# relay-unit-XRF.net
KiCad netlist of a schematic drawn in EAGLE
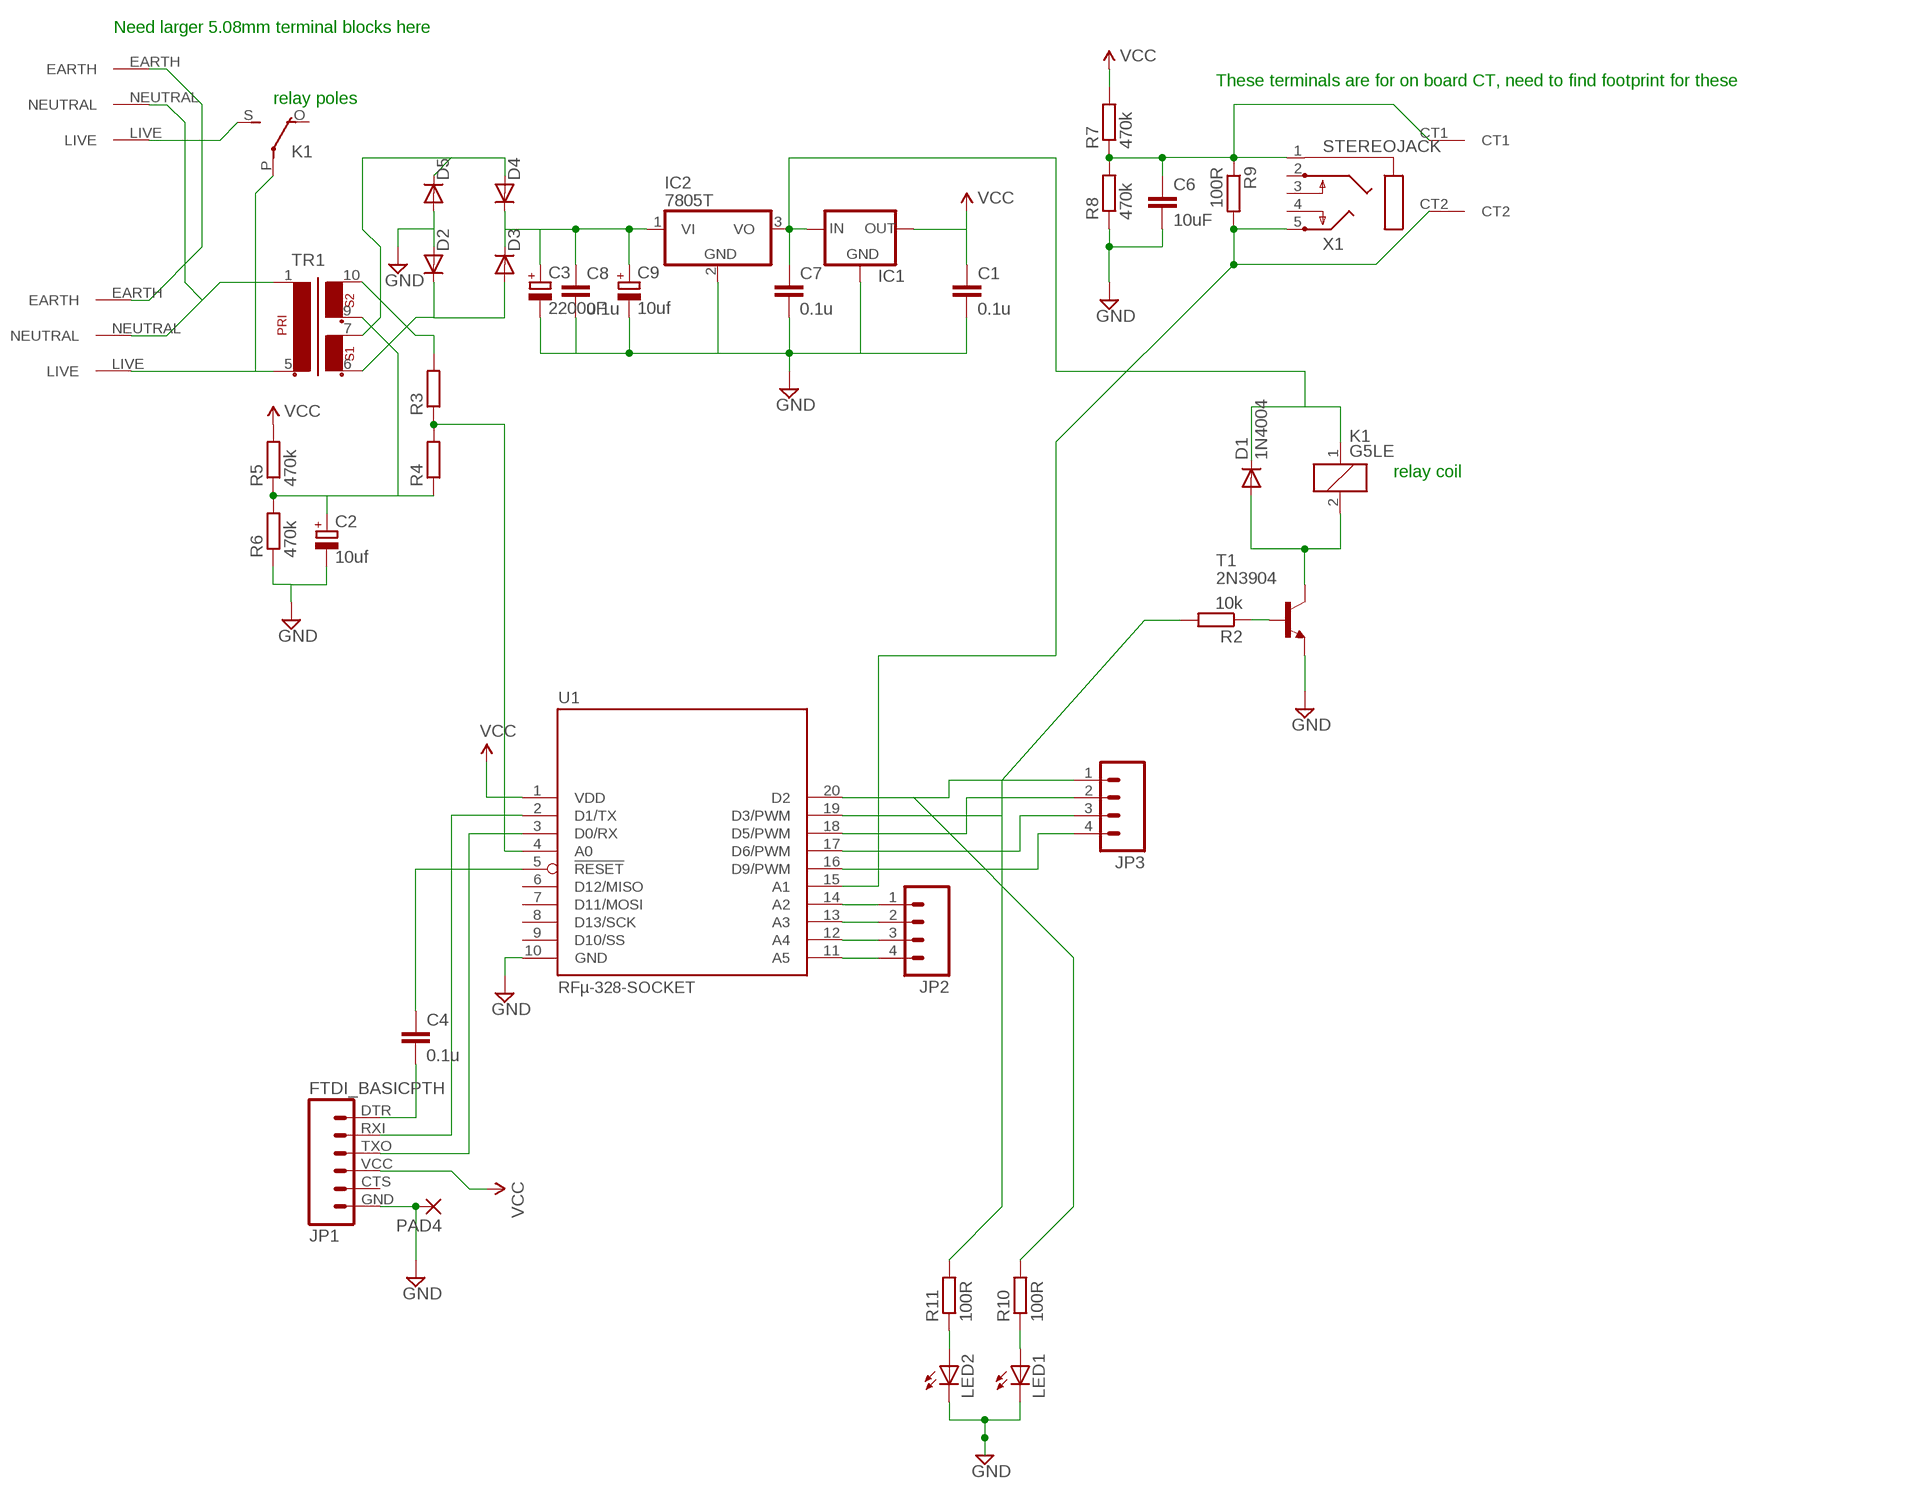
[diagram p0: schematic, sheet 1]

(export (version "E")
  (design (tool "Eeschema 10.0.6"))
  (components
    (comp (ref "C1")
      (value "0.1u")
      (footprint "eagle-import:C025-024X044")
      (libsource (lib "eagle-import") (part "C-EU025-024X044"))
    )
    (comp (ref "C2")
      (value "10uf")
      (footprint "eagle-import:E1,8-4")
      (libsource (lib "eagle-import") (part "CPOL-EUE1.8-4"))
    )
    (comp (ref "C3")
      (value "2200uF")
      (footprint "eagle-import:E5-13")
      (libsource (lib "eagle-import") (part "CPOL-EUE5-13"))
    )
    (comp (ref "C4")
      (value "0.1u")
      (footprint "eagle-import:C025-024X044")
      (libsource (lib "eagle-import") (part "C-EU025-024X044"))
    )
    (comp (ref "C6")
      (value "10uF")
      (footprint "eagle-import:C025-024X044")
      (libsource (lib "eagle-import") (part "C-EU025-024X044"))
    )
    (comp (ref "C7")
      (value "0.1u")
      (footprint "eagle-import:C025-024X044")
      (libsource (lib "eagle-import") (part "C-EU025-024X044"))
    )
    (comp (ref "C8")
      (value "0.1u")
      (footprint "eagle-import:C025-024X044")
      (libsource (lib "eagle-import") (part "C-EU025-024X044"))
    )
    (comp (ref "C9")
      (value "10uf")
      (footprint "eagle-import:E1,8-4")
      (libsource (lib "eagle-import") (part "CPOL-EUE1.8-4"))
    )
    (comp (ref "D1")
      (value "1N4004")
      (footprint "eagle-import:DO41-10")
      (libsource (lib "eagle-import") (part "1N4004"))
    )
    (comp (ref "D2")
      (value "1N4004")
      (footprint "eagle-import:DO41-10")
      (libsource (lib "eagle-import") (part "1N4004"))
    )
    (comp (ref "D3")
      (value "1N4004")
      (footprint "eagle-import:DO41-10")
      (libsource (lib "eagle-import") (part "1N4004"))
    )
    (comp (ref "D4")
      (value "1N4004")
      (footprint "eagle-import:DO41-10")
      (libsource (lib "eagle-import") (part "1N4004"))
    )
    (comp (ref "D5")
      (value "1N4004")
      (footprint "eagle-import:DO41-10")
      (libsource (lib "eagle-import") (part "1N4004"))
    )
    (comp (ref "IC1")
      (value "MCP1700TRI")
      (footprint "eagle-import:TO92")
      (libsource (lib "eagle-import") (part "MCP1700TRI"))
    )
    (comp (ref "IC2")
      (value "7805T")
      (footprint "eagle-import:TO220H")
      (libsource (lib "eagle-import") (part "78T05"))
    )
    (comp (ref "JP1")
      (value "FTDI_BASICPTH")
      (footprint "eagle-import:FTDI_BASIC")
      (libsource (lib "eagle-import") (part "FTDI_BASICPTH"))
    )
    (comp (ref "JP2")
      (value "M04PTH")
      (footprint "eagle-import:1X04")
      (libsource (lib "eagle-import") (part "M04PTH"))
    )
    (comp (ref "JP3")
      (value "M04PTH")
      (footprint "eagle-import:1X04")
      (libsource (lib "eagle-import") (part "M04PTH"))
    )
    (comp (ref "K1")
      (value "G5LE")
      (footprint "eagle-import:G5LE")
      (libsource (lib "eagle-import") (part "G5LE"))
    )
    (comp (ref "LED1")
      (value "LED3MM")
      (footprint "eagle-import:LED3MM")
      (libsource (lib "eagle-import") (part "LED3MM"))
    )
    (comp (ref "LED2")
      (value "LED3MM")
      (footprint "eagle-import:LED3MM")
      (libsource (lib "eagle-import") (part "LED3MM"))
    )
    (comp (ref "PAD4")
      (value "1,6/0,8")
      (footprint "eagle-import:1,6_0,8")
      (libsource (lib "eagle-import") (part "1,6/0,8"))
    )
    (comp (ref "R2")
      (value "10k")
      (footprint "eagle-import:0204_7")
      (libsource (lib "eagle-import") (part "R-EU_0204/7"))
    )
    (comp (ref "R3")
      (value "R-EU_0204/7")
      (footprint "eagle-import:0204_7")
      (libsource (lib "eagle-import") (part "R-EU_0204/7"))
    )
    (comp (ref "R4")
      (value "R-EU_0204/7")
      (footprint "eagle-import:0204_7")
      (libsource (lib "eagle-import") (part "R-EU_0204/7"))
    )
    (comp (ref "R5")
      (value "470k")
      (footprint "eagle-import:0204_7")
      (libsource (lib "eagle-import") (part "R-EU_0204/7"))
    )
    (comp (ref "R6")
      (value "470k")
      (footprint "eagle-import:0204_7")
      (libsource (lib "eagle-import") (part "R-EU_0204/7"))
    )
    (comp (ref "R7")
      (value "470k")
      (footprint "eagle-import:0204_7")
      (libsource (lib "eagle-import") (part "R-EU_0204/7"))
    )
    (comp (ref "R8")
      (value "470k")
      (footprint "eagle-import:0204_7")
      (libsource (lib "eagle-import") (part "R-EU_0204/7"))
    )
    (comp (ref "R9")
      (value "100R")
      (footprint "eagle-import:0204_7")
      (libsource (lib "eagle-import") (part "R-EU_0204/7"))
    )
    (comp (ref "R10")
      (value "100R")
      (footprint "eagle-import:0204_7")
      (libsource (lib "eagle-import") (part "R-EU_0204/7"))
    )
    (comp (ref "R11")
      (value "100R")
      (footprint "eagle-import:0204_7")
      (libsource (lib "eagle-import") (part "R-EU_0204/7"))
    )
    (comp (ref "T1")
      (value "2N3904")
      (footprint "eagle-import:TO92")
      (libsource (lib "eagle-import") (part "2N3904"))
    )
    (comp (ref "TR1")
      (value "EI30-2")
      (footprint "eagle-import:EI30-2")
      (libsource (lib "eagle-import") (part "EI30-2"))
    )
    (comp (ref "U$1")
      (value "TESTTEST")
      (footprint "eagle-import:TEST")
      (libsource (lib "eagle-import") (part "TESTTEST"))
    )
    (comp (ref "U$2")
      (value "AC_IN")
      (footprint "eagle-import:AC_IN")
      (libsource (lib "eagle-import") (part "AC_IN"))
    )
    (comp (ref "U$3") (value "CT") (footprint "eagle-import:CT") (libsource (lib "eagle-import") (part "CT")))
    (comp (ref "U1")
      (value "RFµ-328-SOCKET")
      (footprint "eagle-import:RFµ-328-SOCKET")
      (libsource (lib "eagle-import") (part "RFµ-328-SOCKET"))
    )
    (comp (ref "X1")
      (value "STEREOJACK")
      (footprint "eagle-import:STX3100")
      (libsource (lib "eagle-import") (part "STEREOJACK"))
    )
  )
  (nets
    (net (code "1") (name "GND") (class "Default")
      (node (ref "C1") (pin "2") (pinfunction "2_2") (pintype "passive"))
      (node (ref "C2") (pin "-") (pinfunction "-_-") (pintype "passive"))
      (node (ref "C3") (pin "-") (pinfunction "-_-") (pintype "passive"))
      (node (ref "C6") (pin "2") (pinfunction "2_2") (pintype "passive"))
      (node (ref "C7") (pin "2") (pinfunction "2_2") (pintype "passive"))
      (node (ref "C8") (pin "2") (pinfunction "2_2") (pintype "passive"))
      (node (ref "C9") (pin "-") (pinfunction "-_-") (pintype "passive"))
      (node (ref "D2") (pin "A") (pinfunction "A_A") (pintype "passive"))
      (node (ref "D5") (pin "A") (pinfunction "A_A") (pintype "passive"))
      (node (ref "IC1") (pin "1") (pinfunction "GND_1") (pintype "input"))
      (node (ref "IC2") (pin "2") (pinfunction "GND_2") (pintype "passive"))
      (node (ref "JP1") (pin "GND") (pinfunction "6_GND") (pintype "passive"))
      (node (ref "LED1") (pin "K") (pinfunction "C_K") (pintype "passive"))
      (node (ref "LED2") (pin "K") (pinfunction "C_K") (pintype "passive"))
      (node (ref "PAD4") (pin "1") (pinfunction "P_1") (pintype "passive"))
      (node (ref "R6") (pin "1") (pinfunction "1_1") (pintype "passive"))
      (node (ref "R8") (pin "1") (pinfunction "1_1") (pintype "passive"))
      (node (ref "T1") (pin "3") (pinfunction "E_3") (pintype "passive"))
      (node (ref "U1") (pin "10") (pinfunction "GND_10") (pintype "power_in"))
    )
    (net (code "2") (name "Net-(C6-Pad1)") (class "Default")
      (node (ref "C6") (pin "1") (pinfunction "1_1") (pintype "passive"))
      (node (ref "R7") (pin "1") (pinfunction "1_1") (pintype "passive"))
      (node (ref "R8") (pin "2") (pinfunction "2_2") (pintype "passive"))
      (node (ref "R9") (pin "1") (pinfunction "1_1") (pintype "passive"))
      (node (ref "U$3") (pin "CT1") (pinfunction "CT1_CT1") (pintype "bidirectional"))
      (node (ref "X1") (pin "1") (pinfunction "1_1") (pintype "passive"))
    )
    (net (code "3") (name "Net-(IC1-IN)") (class "Default")
      (node (ref "C7") (pin "1") (pinfunction "1_1") (pintype "passive"))
      (node (ref "D1") (pin "C") (pinfunction "C_C") (pintype "passive"))
      (node (ref "IC1") (pin "2") (pinfunction "IN_2") (pintype "input"))
      (node (ref "IC2") (pin "3") (pinfunction "VO_3") (pintype "passive"))
      (node (ref "K1") (pin "1") (pinfunction "1_1") (pintype "passive"))
    )
    (net (code "4") (name "Net-(IC2-VI)") (class "Default")
      (node (ref "C3") (pin "+") (pinfunction "+_+") (pintype "passive"))
      (node (ref "C8") (pin "1") (pinfunction "1_1") (pintype "passive"))
      (node (ref "C9") (pin "+") (pinfunction "+_+") (pintype "passive"))
      (node (ref "D3") (pin "C") (pinfunction "C_C") (pintype "passive"))
      (node (ref "D4") (pin "C") (pinfunction "C_C") (pintype "passive"))
      (node (ref "IC2") (pin "1") (pinfunction "VI_1") (pintype "input"))
    )
    (net (code "5") (name "Net-(JP1-1)") (class "Default")
      (node (ref "C4") (pin "2") (pinfunction "2_2") (pintype "passive"))
      (node (ref "JP1") (pin "DTR") (pinfunction "1_DTR") (pintype "passive"))
    )
    (net (code "6") (name "Net-(JP1-2)") (class "Default")
      (node (ref "JP1") (pin "RXI") (pinfunction "2_RXI") (pintype "passive"))
      (node (ref "U1") (pin "2") (pinfunction "D1/TX_2") (pintype "output"))
    )
    (net (code "7") (name "Net-(JP1-3)") (class "Default")
      (node (ref "JP1") (pin "TXO") (pinfunction "3_TXO") (pintype "passive"))
      (node (ref "U1") (pin "3") (pinfunction "D0/RX_3") (pintype "input"))
    )
    (net (code "8") (name "Net-(K1-PadS)") (class "Default")
      (node (ref "K1") (pin "S") (pinfunction "S_S") (pintype "passive"))
      (node (ref "U$1") (pin "LIVE") (pinfunction "LIVE_LIVE") (pintype "input"))
    )
    (net (code "9") (name "Net-(LED1-PadA)") (class "Default")
      (node (ref "LED1") (pin "A") (pinfunction "A_A") (pintype "passive"))
      (node (ref "R10") (pin "1") (pinfunction "1_1") (pintype "passive"))
    )
    (net (code "10") (name "Net-(LED2-PadA)") (class "Default")
      (node (ref "LED2") (pin "A") (pinfunction "A_A") (pintype "passive"))
      (node (ref "R11") (pin "1") (pinfunction "1_1") (pintype "passive"))
    )
    (net (code "11") (name "Net-(T1-B)") (class "Default")
      (node (ref "R2") (pin "1") (pinfunction "1_1") (pintype "passive"))
      (node (ref "T1") (pin "2") (pinfunction "B_2") (pintype "passive"))
    )
    (net (code "12") (name "Net-(T1-C)") (class "Default")
      (node (ref "D1") (pin "A") (pinfunction "A_A") (pintype "passive"))
      (node (ref "K1") (pin "2") (pinfunction "2_2") (pintype "passive"))
      (node (ref "T1") (pin "1") (pinfunction "C_1") (pintype "passive"))
    )
    (net (code "13") (name "Net-(TR1-2)") (class "Default")
      (node (ref "K1") (pin "P") (pinfunction "P_P") (pintype "passive"))
      (node (ref "TR1") (pin "5") (pinfunction "2_5") (pintype "passive"))
      (node (ref "U$2") (pin "LIVE") (pinfunction "LIVE_LIVE") (pintype "bidirectional"))
    )
    (net (code "14") (name "Net-(TR1-3)") (class "Default")
      (node (ref "D2") (pin "C") (pinfunction "C_C") (pintype "passive"))
      (node (ref "D3") (pin "A") (pinfunction "A_A") (pintype "passive"))
      (node (ref "TR1") (pin "6") (pinfunction "3_6") (pintype "passive"))
    )
    (net (code "15") (name "Net-(TR1-4)") (class "Default")
      (node (ref "D4") (pin "A") (pinfunction "A_A") (pintype "passive"))
      (node (ref "D5") (pin "C") (pinfunction "C_C") (pintype "passive"))
      (node (ref "TR1") (pin "7") (pinfunction "4_7") (pintype "passive"))
    )
    (net (code "16") (name "Net-(TR1-5)") (class "Default")
      (node (ref "C2") (pin "+") (pinfunction "+_+") (pintype "passive"))
      (node (ref "R4") (pin "1") (pinfunction "1_1") (pintype "passive"))
      (node (ref "R5") (pin "1") (pinfunction "1_1") (pintype "passive"))
      (node (ref "R6") (pin "2") (pinfunction "2_2") (pintype "passive"))
      (node (ref "TR1") (pin "9") (pinfunction "5_9") (pintype "passive"))
    )
    (net (code "17") (name "Net-(TR1-6)") (class "Default")
      (node (ref "R3") (pin "2") (pinfunction "2_2") (pintype "passive"))
      (node (ref "TR1") (pin "10") (pinfunction "6_10") (pintype "passive"))
    )
    (net (code "18") (name "Net-(TR1-Pad1)") (class "Default")
      (node (ref "TR1") (pin "1") (pinfunction "1_1") (pintype "passive"))
      (node (ref "U$1") (pin "NEUTRAL") (pinfunction "NEUTRAL_NEUTRAL") (pintype "input"))
      (node (ref "U$2") (pin "NEUTRAL") (pinfunction "NEUTRAL_NEUTRAL") (pintype "bidirectional"))
    )
    (net (code "19") (name "Net-(U$1-PadEARTH)") (class "Default")
      (node (ref "U$1") (pin "EARTH") (pinfunction "EARTH_EARTH") (pintype "input"))
      (node (ref "U$2") (pin "EARTH") (pinfunction "EARTH_EARTH") (pintype "bidirectional"))
    )
    (net (code "20") (name "Net-(U1-A0)") (class "Default")
      (node (ref "R3") (pin "1") (pinfunction "1_1") (pintype "passive"))
      (node (ref "R4") (pin "2") (pinfunction "2_2") (pintype "passive"))
      (node (ref "U1") (pin "4") (pinfunction "A0_4") (pintype "bidirectional"))
    )
    (net (code "21") (name "Net-(U1-A1)") (class "Default")
      (node (ref "R9") (pin "2") (pinfunction "2_2") (pintype "passive"))
      (node (ref "U$3") (pin "CT2") (pinfunction "CT2_CT2") (pintype "bidirectional"))
      (node (ref "U1") (pin "15") (pinfunction "A1_15") (pintype "bidirectional"))
      (node (ref "X1") (pin "5") (pinfunction "5_5") (pintype "passive"))
    )
    (net (code "22") (name "Net-(U1-A2)") (class "Default")
      (node (ref "JP2") (pin "1") (pinfunction "1_1") (pintype "passive"))
      (node (ref "U1") (pin "14") (pinfunction "A2_14") (pintype "bidirectional"))
    )
    (net (code "23") (name "Net-(U1-A3)") (class "Default")
      (node (ref "JP2") (pin "2") (pinfunction "2_2") (pintype "passive"))
      (node (ref "U1") (pin "13") (pinfunction "A3_13") (pintype "bidirectional"))
    )
    (net (code "24") (name "Net-(U1-A4)") (class "Default")
      (node (ref "JP2") (pin "3") (pinfunction "3_3") (pintype "passive"))
      (node (ref "U1") (pin "12") (pinfunction "A4_12") (pintype "output"))
    )
    (net (code "25") (name "Net-(U1-A5)") (class "Default")
      (node (ref "JP2") (pin "4") (pinfunction "4_4") (pintype "passive"))
      (node (ref "U1") (pin "11") (pinfunction "A5_11") (pintype "bidirectional"))
    )
    (net (code "26") (name "Net-(U1-D2)") (class "Default")
      (node (ref "JP3") (pin "1") (pinfunction "1_1") (pintype "passive"))
      (node (ref "R10") (pin "2") (pinfunction "2_2") (pintype "passive"))
      (node (ref "U1") (pin "20") (pinfunction "D2_20") (pintype "bidirectional"))
    )
    (net (code "27") (name "Net-(U1-D3{slash}PWM)") (class "Default")
      (node (ref "R11") (pin "2") (pinfunction "2_2") (pintype "passive"))
      (node (ref "R2") (pin "2") (pinfunction "2_2") (pintype "passive"))
      (node (ref "U1") (pin "19") (pinfunction "D3/PWM_19") (pintype "bidirectional"))
    )
    (net (code "28") (name "Net-(U1-D5{slash}PWM)") (class "Default")
      (node (ref "JP3") (pin "2") (pinfunction "2_2") (pintype "passive"))
      (node (ref "U1") (pin "18") (pinfunction "D5/PWM_18") (pintype "bidirectional"))
    )
    (net (code "29") (name "Net-(U1-D6{slash}PWM)") (class "Default")
      (node (ref "JP3") (pin "3") (pinfunction "3_3") (pintype "passive"))
      (node (ref "U1") (pin "17") (pinfunction "D6/PWM_17") (pintype "bidirectional"))
    )
    (net (code "30") (name "Net-(U1-D9{slash}PWM)") (class "Default")
      (node (ref "JP3") (pin "4") (pinfunction "4_4") (pintype "passive"))
      (node (ref "U1") (pin "16") (pinfunction "D9/PWM_16") (pintype "input"))
    )
    (net (code "31") (name "Net-(U1-~{RESET})") (class "Default")
      (node (ref "C4") (pin "1") (pinfunction "1_1") (pintype "passive"))
      (node (ref "U1") (pin "5") (pinfunction "~{RESET}_5") (pintype "input"))
    )
    (net (code "32") (name "VCC") (class "Default")
      (node (ref "C1") (pin "1") (pinfunction "1_1") (pintype "passive"))
      (node (ref "IC1") (pin "3") (pinfunction "OUT_3") (pintype "passive"))
      (node (ref "JP1") (pin "VCC") (pinfunction "4_VCC") (pintype "passive"))
      (node (ref "R5") (pin "2") (pinfunction "2_2") (pintype "passive"))
      (node (ref "R7") (pin "2") (pinfunction "2_2") (pintype "passive"))
      (node (ref "U1") (pin "1") (pinfunction "VDD_1") (pintype "power_in"))
    )
    (net (code "33") (name "unconnected-(JP1-5-PadCTS)") (class "Default")
      (node (ref "JP1") (pin "CTS") (pinfunction "5_CTS") (pintype "passive"))
    )
    (net (code "34") (name "unconnected-(K1-PadO)") (class "Default")
      (node (ref "K1") (pin "O") (pinfunction "O_O") (pintype "passive"))
    )
    (net (code "35") (name "unconnected-(U1-D10{slash}SS-Pad9)") (class "Default")
      (node (ref "U1") (pin "9") (pinfunction "D10/SS_9") (pintype "bidirectional"))
    )
    (net (code "36") (name "unconnected-(U1-D11{slash}MOSI-Pad7)") (class "Default")
      (node (ref "U1") (pin "7") (pinfunction "D11/MOSI_7") (pintype "bidirectional"))
    )
    (net (code "37") (name "unconnected-(U1-D12{slash}MISO-Pad6)") (class "Default")
      (node (ref "U1") (pin "6") (pinfunction "D12/MISO_6") (pintype "bidirectional"))
    )
    (net (code "38") (name "unconnected-(U1-D13{slash}SCK-Pad8)") (class "Default")
      (node (ref "U1") (pin "8") (pinfunction "D13/SCK_8") (pintype "bidirectional"))
    )
    (net (code "39") (name "unconnected-(X1-Pad2)") (class "Default")
      (node (ref "X1") (pin "2") (pinfunction "2_2") (pintype "passive"))
    )
    (net (code "40") (name "unconnected-(X1-Pad3)") (class "Default")
      (node (ref "X1") (pin "3") (pinfunction "3_3") (pintype "passive"))
    )
    (net (code "41") (name "unconnected-(X1-Pad4)") (class "Default")
      (node (ref "X1") (pin "4") (pinfunction "4_4") (pintype "passive"))
    )
  )
)
